# BalanceCar.net
KiCad netlist of a schematic drawn in Altium Designer
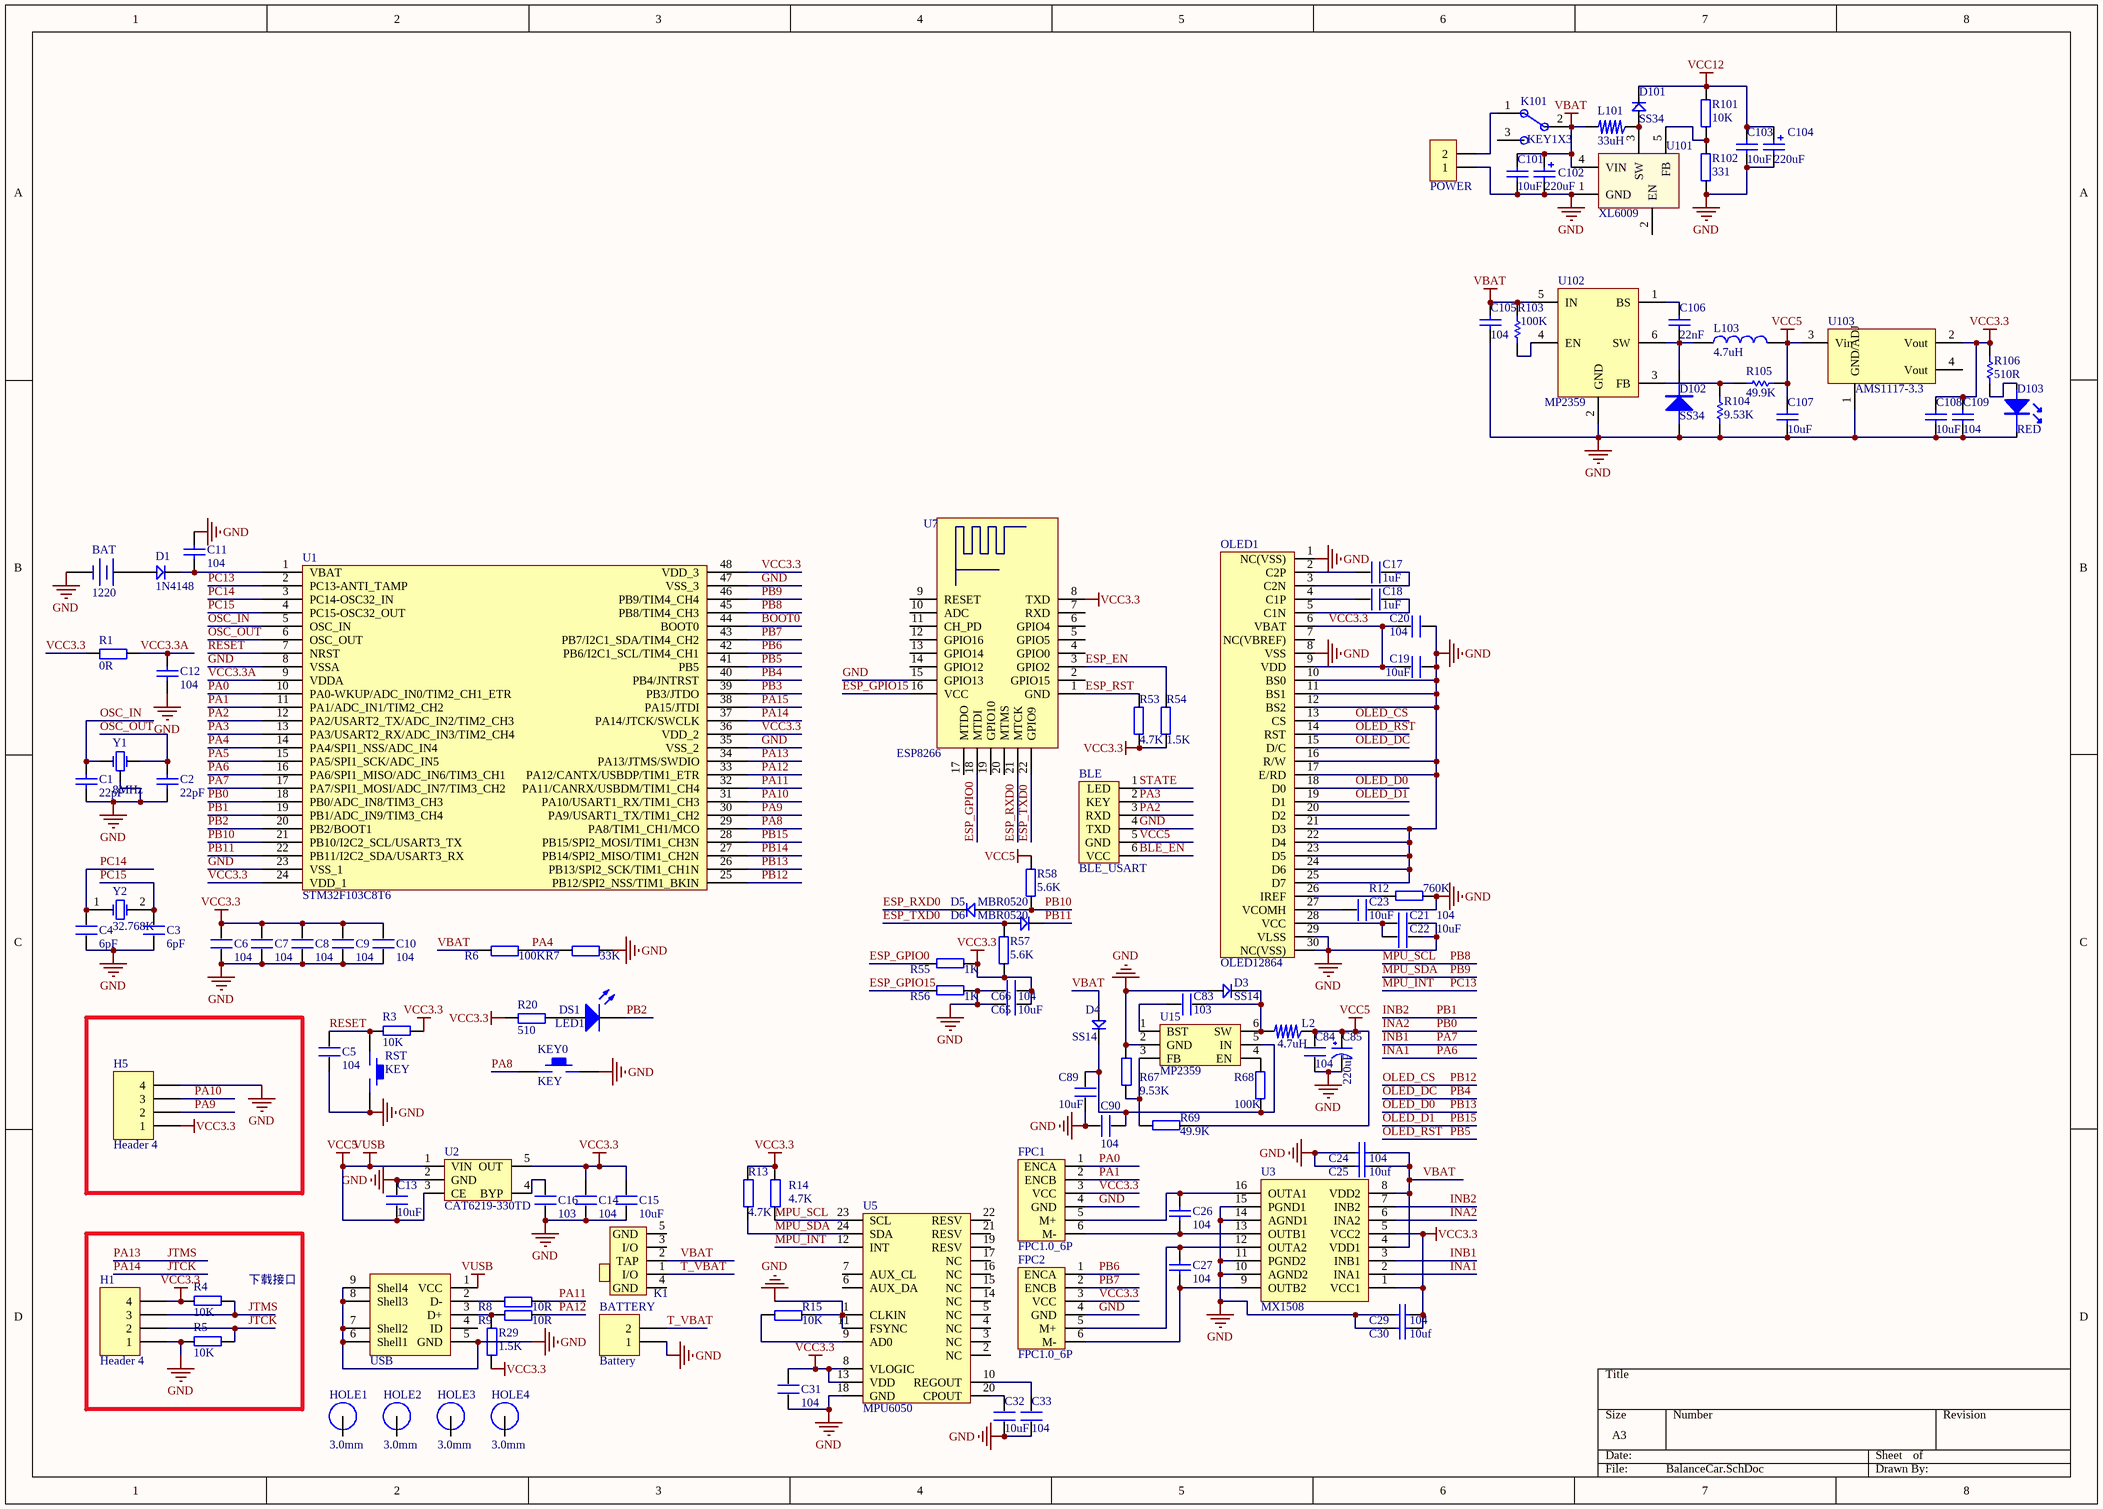
[diagram p0: BalanceCar.SchDoc]

(export (version "E")
  (design (tool "Eeschema 10.0.6"))
  (components
    (comp (ref "BAT")
      (value "1220")
      (footprint "CR1220_B")
      (description "微型电池")
      (libsource (lib "IMX6UL_ALPHA(底板)_V2.0") (part "CR-3V"))
    )
    (comp (ref "BATTERY")
      (value "Battery")
      (footprint "HDR2.54-LI-2P")
      (description "Header, 2-Pin")
      (fields (field (name "PUBLISHER") "Altium Limited"))
      (libsource (lib "WarShip V3 STM32103封装库") (part "Header 2"))
    )
    (comp (ref "BLE")
      (value "BLE_USART")
      (footprint "HEAD6")
      (description "ATK-HC05")
      (libsource (lib "阿波罗STM32F4&F7&H7底板封装库") (part "ATK-HC05"))
    )
    (comp (ref "C1") (value "22pF") (footprint "C 0603_M") (libsource (lib "L476") (part "CAP")))
    (comp (ref "C2") (value "22pF") (footprint "C 0603_M") (libsource (lib "L476") (part "CAP")))
    (comp (ref "C3")
      (value "6pF")
      (footprint "C 0603_M")
      (libsource (lib "WarShip V3 STM32103封装库") (part "C"))
    )
    (comp (ref "C4")
      (value "6pF")
      (footprint "C 0603_M")
      (libsource (lib "WarShip V3 STM32103封装库") (part "C"))
    )
    (comp (ref "C5")
      (value "104")
      (footprint "C 0603_M")
      (libsource (lib "WarShip V3 STM32103封装库") (part "C"))
    )
    (comp (ref "C6")
      (value "104")
      (footprint "C 0603_M")
      (libsource (lib "WarShip V3 STM32103封装库") (part "C"))
    )
    (comp (ref "C7")
      (value "104")
      (footprint "C 0603_M")
      (libsource (lib "WarShip V3 STM32103封装库") (part "C"))
    )
    (comp (ref "C8")
      (value "104")
      (footprint "C 0603_M")
      (libsource (lib "WarShip V3 STM32103封装库") (part "C"))
    )
    (comp (ref "C9")
      (value "104")
      (footprint "C 0603_M")
      (libsource (lib "WarShip V3 STM32103封装库") (part "C"))
    )
    (comp (ref "C10")
      (value "104")
      (footprint "C 0603_M")
      (libsource (lib "WarShip V3 STM32103封装库") (part "C"))
    )
    (comp (ref "C11") (value "104") (footprint "C 0603_M") (libsource (lib "L476") (part "CAP")))
    (comp (ref "C12") (value "104") (footprint "C 0603_M") (libsource (lib "L476") (part "CAP")))
    (comp (ref "C13")
      (value "10uF")
      (footprint "C 0603_M")
      (libsource (lib "WarShip V3 STM32103封装库") (part "C"))
    )
    (comp (ref "C14")
      (value "104")
      (footprint "C 0603_M")
      (libsource (lib "WarShip V3 STM32103封装库") (part "C"))
    )
    (comp (ref "C15")
      (value "10uF")
      (footprint "C 0603_M")
      (libsource (lib "WarShip V3 STM32103封装库") (part "C"))
    )
    (comp (ref "C16")
      (value "103")
      (footprint "C 0603_M")
      (libsource (lib "WarShip V3 STM32103封装库") (part "C"))
    )
    (comp (ref "C17")
      (value "1uF")
      (footprint "C 0603_M")
      (libsource (lib "WarShip V3 STM32103封装库") (part "C"))
    )
    (comp (ref "C18")
      (value "1uF")
      (footprint "C 0603_M")
      (libsource (lib "WarShip V3 STM32103封装库") (part "C"))
    )
    (comp (ref "C19")
      (value "10uF")
      (footprint "C 0603_M")
      (libsource (lib "WarShip V3 STM32103封装库") (part "C"))
    )
    (comp (ref "C20")
      (value "104")
      (footprint "C 0603_M")
      (libsource (lib "WarShip V3 STM32103封装库") (part "C"))
    )
    (comp (ref "C21")
      (value "10uF")
      (footprint "C 0603_M")
      (libsource (lib "WarShip V3 STM32103封装库") (part "C"))
    )
    (comp (ref "C22")
      (value "104")
      (footprint "C 0603_M")
      (libsource (lib "WarShip V3 STM32103封装库") (part "C"))
    )
    (comp (ref "C23")
      (value "10uF")
      (footprint "C 0603_M")
      (libsource (lib "WarShip V3 STM32103封装库") (part "C"))
    )
    (comp (ref "C24") (value "104") (footprint "C 0603_M") (libsource (lib "L476") (part "CAP")))
    (comp (ref "C25") (value "10uf") (footprint "C 0603_M") (libsource (lib "L476") (part "CAP")))
    (comp (ref "C26") (value "104") (footprint "C 0603_M") (libsource (lib "L476") (part "CAP")))
    (comp (ref "C27") (value "104") (footprint "C 0603_M") (libsource (lib "L476") (part "CAP")))
    (comp (ref "C29") (value "104") (footprint "C 0603_M") (libsource (lib "L476") (part "CAP")))
    (comp (ref "C30") (value "10uf") (footprint "C 0603_M") (libsource (lib "L476") (part "CAP")))
    (comp (ref "C31")
      (value "104")
      (footprint "C 0603_M")
      (libsource (lib "WarShip V3 STM32103封装库") (part "C"))
    )
    (comp (ref "C32")
      (value "10uF")
      (footprint "C 0603_M")
      (libsource (lib "WarShip V3 STM32103封装库") (part "C"))
    )
    (comp (ref "C33")
      (value "104")
      (footprint "C 0603_M")
      (libsource (lib "WarShip V3 STM32103封装库") (part "C"))
    )
    (comp (ref "C65") (value "10uF") (footprint "C 0603_M") (libsource (lib "ATK-OV5640摄像头模块封装库") (part "C")))
    (comp (ref "C66") (value "104") (footprint "C 0603_M") (libsource (lib "ATK-OV5640摄像头模块封装库") (part "C")))
    (comp (ref "C83") (value "103") (footprint "C 0603_M") (libsource (lib "ALIENTEK_COMPONENT") (part "C")))
    (comp (ref "C84") (value "104") (footprint "C 0603_M") (libsource (lib "MYCOMLIB") (part "C")))
    (comp (ref "C85") (value "220uF") (footprint "CM D(6.3*5.4)") (libsource (lib "MYCOMLIB") (part "CAP")))
    (comp (ref "C89") (value "10uF") (footprint "C 1206_L") (libsource (lib "ALIENTEK_COMPONENT") (part "C")))
    (comp (ref "C90") (value "104") (footprint "C 0603_M") (libsource (lib "MYCOMLIB") (part "C")))
    (comp (ref "C101")
      (value "10uF")
      (footprint "C 1210_M")
      (description "Capacitor")
      (fields (field (name "Comment") "Cap") (field (name "PUBLISHER") "Altium Limited"))
      (libsource (lib "YS_BDC_V1") (part "Cap_1"))
    )
    (comp (ref "C102")
      (value "220uF")
      (footprint "CAP 3.5*8*11.5 - BK")
      (description "Polarized Capacitor (Radial)")
      (fields (field (name "Comment") "Cap Pol") (field (name "PUBLISHER") "Altium Limited"))
      (libsource (lib "YS_BDC_V1") (part "Cap Pol_1"))
    )
    (comp (ref "C103")
      (value "10uF")
      (footprint "C 1210_M")
      (description "Capacitor")
      (fields (field (name "Comment") "Cap") (field (name "PUBLISHER") "Altium Limited"))
      (libsource (lib "YS_BDC_V1") (part "Cap_1"))
    )
    (comp (ref "C104")
      (value "220uF")
      (footprint "CAP 3.5*8*11.5 - BK")
      (description "Polarized Capacitor (Radial)")
      (fields (field (name "Comment") "Cap Pol") (field (name "PUBLISHER") "Altium Limited"))
      (libsource (lib "YS_BDC_V1") (part "Cap Pol_1"))
    )
    (comp (ref "C105")
      (value "104")
      (footprint "C 0603_M")
      (description "Capacitor")
      (fields (field (name "Comment") "Cap") (field (name "PUBLISHER") "Altium Limited"))
      (libsource (lib "YS_BLDC&PMSM") (part "Cap"))
    )
    (comp (ref "C106")
      (value "22nF")
      (footprint "C 0603_M")
      (description "Capacitor")
      (fields (field (name "Comment") "Cap") (field (name "PUBLISHER") "Altium Limited"))
      (libsource (lib "YS_BLDC&PMSM") (part "Cap"))
    )
    (comp (ref "C107")
      (value "10uF")
      (footprint "C 1210_M")
      (description "Capacitor")
      (fields (field (name "Comment") "Cap") (field (name "PUBLISHER") "Altium Limited"))
      (libsource (lib "YS_BDC_V1") (part "Cap_1"))
    )
    (comp (ref "C108")
      (value "10uF")
      (footprint "C 1210_M")
      (description "Capacitor")
      (fields (field (name "Comment") "Cap") (field (name "PUBLISHER") "Altium Limited"))
      (libsource (lib "YS_BDC_V1") (part "Cap_1"))
    )
    (comp (ref "C109")
      (value "104")
      (footprint "C 0603_M")
      (description "Capacitor")
      (fields (field (name "Comment") "Cap") (field (name "PUBLISHER") "Altium Limited"))
      (libsource (lib "YS_BLDC&PMSM") (part "Cap"))
    )
    (comp (ref "D1")
      (value "1N4148")
      (footprint "MINI_MELF (LL34)")
      (libsource (lib "阿波罗STM32F4&F7底板封装库") (part "D"))
    )
    (comp (ref "D3")
      (value "SS14")
      (footprint "SMA")
      (description "1N4148")
      (libsource (lib "MYCOMLIB") (part "D"))
    )
    (comp (ref "D4")
      (value "SS14")
      (footprint "SMA")
      (description "1N4148")
      (libsource (lib "MYCOMLIB") (part "D"))
    )
    (comp (ref "D5")
      (value "MBR0520")
      (footprint "SOD-123")
      (description "1N4148")
      (libsource (lib "ESP8266V1.2") (part "D"))
    )
    (comp (ref "D6")
      (value "MBR0520")
      (footprint "SOD-123")
      (description "1N4148")
      (libsource (lib "ESP8266V1.2") (part "D"))
    )
    (comp (ref "D101") (value "SS34") (footprint "SMA") (libsource (lib "阿波罗STM32F4&F7&H7底板封装库") (part "D")))
    (comp (ref "D102")
      (value "SS34")
      (footprint "SMA")
      (description "Diode")
      (libsource (lib "YS_BDC_V1") (part "DIODE_1"))
    )
    (comp (ref "D103") (value "RED") (footprint "LED 0805R") (libsource (lib "YS_BLDC&PMSM") (part "LED")))
    (comp (ref "DS1")
      (value "LED1")
      (footprint "LED 0603R")
      (description "Typical RED, GREEN, YELLOW, AMBER GaAs LED")
      (fields (field (name "PUBLISHER") "Altium Limited"))
      (libsource (lib "WarShip V3 STM32103封装库") (part "LED2"))
    )
    (comp (ref "FPC1")
      (value "FPC1.0_6P")
      (footprint "FPC_1.0_6P")
      (libsource (lib "MOTOR_FPC") (part "FPC"))
    )
    (comp (ref "FPC2")
      (value "FPC1.0_6P")
      (footprint "FPC_1.0_6P")
      (libsource (lib "MOTOR_FPC") (part "FPC"))
    )
    (comp (ref "H1")
      (value "Header 4")
      (footprint "HDR2.54-LI-4P")
      (description "Header, 4-Pin")
      (fields (field (name "PUBLISHER") "Altium Limited"))
      (libsource (lib "WarShip V3 STM32103封装库") (part "Header 4"))
    )
    (comp (ref "H5")
      (value "Header 4")
      (footprint "HDR2.54-LI-4P")
      (description "Header, 4-Pin")
      (fields (field (name "PUBLISHER") "Altium Limited"))
      (libsource (lib "WarShip V3 STM32103封装库") (part "Header 4"))
    )
    (comp (ref "HOLE1")
      (value "3.0mm")
      (footprint "HOLE-M3")
      (fields (field (name "Comment") "HOLE"))
      (libsource (lib "YS_BDC_V1") (part "HOLE"))
    )
    (comp (ref "HOLE2")
      (value "3.0mm")
      (footprint "HOLE-M3")
      (fields (field (name "Comment") "HOLE"))
      (libsource (lib "YS_BDC_V1") (part "HOLE"))
    )
    (comp (ref "HOLE3")
      (value "3.0mm")
      (footprint "HOLE-M3")
      (fields (field (name "Comment") "HOLE"))
      (libsource (lib "YS_BDC_V1") (part "HOLE"))
    )
    (comp (ref "HOLE4")
      (value "3.0mm")
      (footprint "HOLE-M3")
      (fields (field (name "Comment") "HOLE"))
      (libsource (lib "YS_BDC_V1") (part "HOLE"))
    )
    (comp (ref "K1")
      (value "BUTTON_DIP3")
      (footprint "BTN8.8*4.6")
      (description "拨动开关SS-12F44")
      (libsource (lib "Pandora_STM32L4_Board_V2.4") (part "BUTTON_DIP3"))
    )
    (comp (ref "K101")
      (value "KEY1X3")
      (footprint "PKEY")
      (libsource (lib "IMX6UL_ALPHA(底板)_V2.0") (part "PKEY"))
    )
    (comp (ref "KEY0")
      (value "KEY")
      (footprint "TSW SMD-3*6*2.5")
      (libsource (lib "STM32F429核心板封装库") (part "KEY_M"))
    )
    (comp (ref "L2")
      (value "4.7uH")
      (footprint "CDRH73")
      (libsource (lib "ALIENTEK_COMPONENT") (part "L_SOP"))
    )
    (comp (ref "L101")
      (value "33uH")
      (footprint "L_SOP74")
      (libsource (lib "阿波罗STM32F4&F7&H7底板封装库") (part "L_SOP"))
    )
    (comp (ref "L103")
      (value "4.7uH")
      (footprint "CD73")
      (fields (field (name "Comment") "Inductance"))
      (libsource (lib "YS_BDC_V1") (part "Inductance"))
    )
    (comp (ref "OLED1")
      (value "OLED12864")
      (footprint "OLED12864")
      (libsource (lib "OLED模块封装库") (part "OLED12864"))
    )
    (comp (ref "POWER")
      (value "SPKL")
      (footprint "XH2.54-2P_H")
      (description "2P接插件")
      (libsource (lib "IMX6UL_ALPHA(底板)_V2.0") (part "Header 2"))
    )
    (comp (ref "R1")
      (value "0R")
      (footprint "R 0603_M")
      (libsource (lib "WarShip V3 STM32103封装库") (part "R"))
    )
    (comp (ref "R3")
      (value "10K")
      (footprint "R 0603_M")
      (libsource (lib "WarShip V3 STM32103封装库") (part "R"))
    )
    (comp (ref "R4")
      (value "10K")
      (footprint "R 0603_M")
      (libsource (lib "WarShip V3 STM32103封装库") (part "R"))
    )
    (comp (ref "R5")
      (value "10K")
      (footprint "R 0603_M")
      (libsource (lib "WarShip V3 STM32103封装库") (part "R"))
    )
    (comp (ref "R6")
      (value "100K")
      (footprint "R 0603_M")
      (libsource (lib "WarShip V3 STM32103封装库") (part "R"))
    )
    (comp (ref "R7")
      (value "33K")
      (footprint "R 0603_M")
      (libsource (lib "WarShip V3 STM32103封装库") (part "R"))
    )
    (comp (ref "R8")
      (value "10R")
      (footprint "R 0603_M")
      (libsource (lib "WarShip V3 STM32103封装库") (part "R"))
    )
    (comp (ref "R9")
      (value "10R")
      (footprint "R 0603_M")
      (libsource (lib "WarShip V3 STM32103封装库") (part "R"))
    )
    (comp (ref "R12")
      (value "760K")
      (footprint "R 0603_M")
      (libsource (lib "WarShip V3 STM32103封装库") (part "R"))
    )
    (comp (ref "R13")
      (value "4.7K")
      (footprint "R 0603_M")
      (libsource (lib "WarShip V3 STM32103封装库") (part "R"))
    )
    (comp (ref "R14")
      (value "4.7K")
      (footprint "R 0603_M")
      (libsource (lib "WarShip V3 STM32103封装库") (part "R"))
    )
    (comp (ref "R15")
      (value "10K")
      (footprint "R 0603_M")
      (libsource (lib "WarShip V3 STM32103封装库") (part "R"))
    )
    (comp (ref "R20")
      (value "510")
      (footprint "R 0603_M")
      (libsource (lib "WarShip V3 STM32103封装库") (part "R"))
    )
    (comp (ref "R29")
      (value "1.5K")
      (footprint "R 0603_M")
      (libsource (lib "WarShip V3 STM32103封装库") (part "R"))
    )
    (comp (ref "R53")
      (value "4.7K")
      (footprint "R 0603_M")
      (libsource (lib "WarShip V3 STM32103封装库") (part "R"))
    )
    (comp (ref "R54")
      (value "1.5K")
      (footprint "R 0603_M")
      (libsource (lib "WarShip V3 STM32103封装库") (part "R"))
    )
    (comp (ref "R55")
      (value "1K")
      (footprint "R 0603_M")
      (libsource (lib "WarShip V3 STM32103封装库") (part "R"))
    )
    (comp (ref "R56")
      (value "1K")
      (footprint "R 0603_M")
      (libsource (lib "WarShip V3 STM32103封装库") (part "R"))
    )
    (comp (ref "R57")
      (value "5.6K")
      (footprint "R 0603_M")
      (libsource (lib "WarShip V3 STM32103封装库") (part "R"))
    )
    (comp (ref "R58")
      (value "5.6K")
      (footprint "R 0603_M")
      (libsource (lib "WarShip V3 STM32103封装库") (part "R"))
    )
    (comp (ref "R67")
      (value "9.53K")
      (footprint "R 0603_M")
      (libsource (lib "ALIENTEK_COMPONENT") (part "R"))
    )
    (comp (ref "R68") (value "100K") (footprint "R 0603_M") (libsource (lib "ALIENTEK_COMPONENT") (part "R")))
    (comp (ref "R69")
      (value "49.9K")
      (footprint "R 0603_M")
      (libsource (lib "ALIENTEK_COMPONENT") (part "R"))
    )
    (comp (ref "R101") (value "10K") (footprint "3296W") (libsource (lib "阿波罗STM32F4&F7&H7底板封装库") (part "R")))
    (comp (ref "R102")
      (value "331")
      (footprint "R 0603_M")
      (libsource (lib "阿波罗STM32F4&F7&H7底板封装库") (part "R"))
    )
    (comp (ref "R103")
      (value "100K")
      (footprint "R 0603_M")
      (description "Resistor")
      (fields (field (name "Comment") "Res1") (field (name "PUBLISHER") "Altium Limited"))
      (libsource (lib "YS_BLDC&PMSM") (part "Res1"))
    )
    (comp (ref "R104")
      (value "9.53K")
      (footprint "R 0603_M")
      (description "Resistor")
      (fields (field (name "Comment") "Res1") (field (name "PUBLISHER") "Altium Limited"))
      (libsource (lib "YS_BLDC&PMSM") (part "Res1"))
    )
    (comp (ref "R105")
      (value "49.9K")
      (footprint "R 0603_M")
      (description "Resistor")
      (fields (field (name "Comment") "Res1") (field (name "PUBLISHER") "Altium Limited"))
      (libsource (lib "YS_BLDC&PMSM") (part "Res1"))
    )
    (comp (ref "R106")
      (value "510R")
      (footprint "R 0603_M")
      (description "Resistor")
      (fields (field (name "Comment") "Res1") (field (name "PUBLISHER") "Altium Limited"))
      (libsource (lib "YS_BLDC&PMSM") (part "Res1"))
    )
    (comp (ref "RST") (value "KEY") (footprint "TSW SMD-3*6*2.5") (libsource (lib "") (part "KEY_M_1")))
    (comp (ref "U1")
      (value "STM32F103C8T6")
      (footprint "LQFP-48PIN")
      (libsource (lib "Pandora_STM32L4_Board_V2.4") (part "U-STM32F103C8T6"))
    )
    (comp (ref "U2")
      (value "CAT6219-330TD")
      (footprint "SOT23-5M")
      (description "3.3V 500mA LDO")
      (libsource (lib "STM32H743核心板封装库") (part "CAT6219-330TD"))
    )
    (comp (ref "U3") (value "MX1508") (footprint "SOP16N_M") (libsource (lib "fan") (part "Component_1")))
    (comp (ref "U5")
      (value "MPU6050")
      (footprint "QFN24 4x4_N")
      (description "9轴运动处理传感器")
      (libsource (lib "ATK-MPU6050六轴传感器模块") (part "MPU6050"))
    )
    (comp (ref "U7") (value "ESP8266") (footprint "ESP_12E") (libsource (lib "ESP8266V1.2") (part "ESP8266")))
    (comp (ref "U15")
      (value "MP2359")
      (footprint "SOT23-6M")
      (description "DC DC Step Down IC")
      (libsource (lib "ALIENTEK_COMPONENT") (part "MP2359"))
    )
    (comp (ref "U101") (value "XL6009") (footprint "TO-263-5") (libsource (lib "POWER") (part "XL6009")))
    (comp (ref "U102")
      (value "MP2359")
      (footprint "SOT23-6M")
      (description "MP2359DJ-LF-Z")
      (libsource (lib "YS_BDC_V1") (part "MP2359"))
    )
    (comp (ref "U103")
      (value "AMS1117-3.3")
      (footprint "SOT223_N")
      (description "LDO 3.3V")
      (libsource (lib "YS_BLDC&PMSM") (part "AMS1117-3.3"))
    )
    (comp (ref "USB")
      (value "J-MICRO-USB-5S")
      (footprint "USB-AB-5S")
      (description "Micro USB 5.9有柱脚长1.25加长针")
      (libsource (lib "Pandora_STM32L4_Board_V2.4") (part "J-MICRO-USB-5S"))
    )
    (comp (ref "Y1")
      (value "8MHz")
      (footprint "Y-XTAL-3215-3P")
      (description "XTAL,3215,8MHz")
      (libsource (lib "Pandora_STM32L4_Board_V2.4") (part "Y-3215-8M"))
    )
    (comp (ref "Y2")
      (value "32.768K")
      (footprint "OSC 3215-2P")
      (description "Crystal Oscillator")
      (fields (field (name "PUBLISHER") "Altium Limited"))
      (libsource (lib "WarShip V3 STM32103封装库") (part "XTAL"))
    )
  )
  (nets
    (net (code "1") (name "/BLE_EN") (class "Default")
      (node (ref "BLE") (pin "6") (pinfunction "VCC_6") (pintype "passive"))
    )
    (net (code "2") (name "/BOOT0") (class "Default")
      (node (ref "U1") (pin "44") (pinfunction "BOOT0_44") (pintype "passive"))
    )
    (net (code "3") (name "/ESP_EN") (class "Default")
      (node (ref "R54") (pin "1") (pintype "passive"))
      (node (ref "U7") (pin "3") (pinfunction "GPIO2_3") (pintype "passive"))
    )
    (net (code "4") (name "/ESP_GPIO0") (class "Default")
      (node (ref "R55") (pin "2") (pintype "passive"))
      (node (ref "U7") (pin "18") (pinfunction "MTDI_18") (pintype "passive"))
    )
    (net (code "5") (name "/ESP_GPIO15") (class "Default")
      (node (ref "R56") (pin "2") (pintype "passive"))
      (node (ref "U7") (pin "16") (pinfunction "VCC_16") (pintype "passive"))
    )
    (net (code "6") (name "/ESP_RST") (class "Default")
      (node (ref "R53") (pin "1") (pintype "passive"))
      (node (ref "U7") (pin "1") (pinfunction "GND_1") (pintype "open_emitter"))
    )
    (net (code "7") (name "/ESP_RXD0") (class "Default")
      (node (ref "D5") (pin "2") (pintype "passive"))
      (node (ref "U7") (pin "21") (pinfunction "MTCK_21") (pintype "passive"))
    )
    (net (code "8") (name "/ESP_TXD0") (class "Default")
      (node (ref "D6") (pin "1") (pintype "passive"))
      (node (ref "R57") (pin "1") (pintype "passive"))
      (node (ref "U7") (pin "22") (pinfunction "GPIO9_22") (pintype "passive"))
    )
    (net (code "9") (name "/INA1") (class "Default")
      (node (ref "U1") (pin "16") (pinfunction "PA6/SPI1_MISO/ADC_IN6/TIM3_CH1_16") (pintype "passive"))
      (node (ref "U3") (pin "2") (pinfunction "INA1_2") (pintype "passive"))
    )
    (net (code "10") (name "/INA2") (class "Default")
      (node (ref "U1") (pin "18") (pinfunction "PB0/ADC_IN8/TIM3_CH3_18") (pintype "passive"))
      (node (ref "U3") (pin "6") (pinfunction "INA2_6") (pintype "passive"))
    )
    (net (code "11") (name "/INB1") (class "Default")
      (node (ref "U1") (pin "17") (pinfunction "PA7/SPI1_MOSI/ADC_IN7/TIM3_CH2_17") (pintype "passive"))
      (node (ref "U3") (pin "3") (pinfunction "INB1_3") (pintype "passive"))
    )
    (net (code "12") (name "/INB2") (class "Default")
      (node (ref "U1") (pin "19") (pinfunction "PB1/ADC_IN9/TIM3_CH4_19") (pintype "passive"))
      (node (ref "U3") (pin "7") (pinfunction "INB2_7") (pintype "passive"))
    )
    (net (code "13") (name "/JTCK") (class "Default")
      (node (ref "H1") (pin "2") (pinfunction "2_2") (pintype "passive"))
      (node (ref "R5") (pin "1") (pintype "passive"))
      (node (ref "U1") (pin "37") (pinfunction "PA14/JTCK/SWCLK_37") (pintype "passive"))
    )
    (net (code "14") (name "/JTMS") (class "Default")
      (node (ref "H1") (pin "3") (pinfunction "3_3") (pintype "passive"))
      (node (ref "R4") (pin "1") (pintype "passive"))
      (node (ref "U1") (pin "34") (pinfunction "PA13/JTMS/SWDIO_34") (pintype "passive"))
    )
    (net (code "15") (name "/MPU_INT") (class "Default")
      (node (ref "U1") (pin "2") (pinfunction "PC13-ANTI_TAMP_2") (pintype "passive"))
      (node (ref "U5") (pin "12") (pinfunction "INT_12") (pintype "passive"))
    )
    (net (code "16") (name "/MPU_SCL") (class "Default")
      (node (ref "R14") (pin "1") (pintype "passive"))
      (node (ref "U1") (pin "45") (pinfunction "PB8/TIM4_CH3_45") (pintype "passive"))
      (node (ref "U5") (pin "23") (pinfunction "SCL_23") (pintype "passive"))
    )
    (net (code "17") (name "/MPU_SDA") (class "Default")
      (node (ref "R13") (pin "1") (pintype "passive"))
      (node (ref "U1") (pin "46") (pinfunction "PB9/TIM4_CH4_46") (pintype "passive"))
      (node (ref "U5") (pin "24") (pinfunction "SDA_24") (pintype "passive"))
    )
    (net (code "18") (name "/OLED_CS") (class "Default")
      (node (ref "OLED1") (pin "13") (pinfunction "CS_13") (pintype "passive"))
      (node (ref "U1") (pin "25") (pinfunction "PB12/SPI2_NSS/TIM1_BKIN_25") (pintype "passive"))
    )
    (net (code "19") (name "/OLED_D0") (class "Default")
      (node (ref "OLED1") (pin "18") (pinfunction "D0_18") (pintype "passive"))
      (node (ref "U1") (pin "26") (pinfunction "PB13/SPI2_SCK/TIM1_CH1N_26") (pintype "passive"))
    )
    (net (code "20") (name "/OLED_D1") (class "Default")
      (node (ref "OLED1") (pin "19") (pinfunction "D1_19") (pintype "passive"))
      (node (ref "U1") (pin "28") (pinfunction "PB15/SPI2_MOSI/TIM1_CH3N_28") (pintype "passive"))
    )
    (net (code "21") (name "/OLED_DC") (class "Default")
      (node (ref "OLED1") (pin "15") (pinfunction "D/C_15") (pintype "passive"))
      (node (ref "U1") (pin "40") (pinfunction "PB4/JNTRST_40") (pintype "passive"))
    )
    (net (code "22") (name "/OLED_RST") (class "Default")
      (node (ref "OLED1") (pin "14") (pinfunction "RST_14") (pintype "passive"))
      (node (ref "U1") (pin "41") (pinfunction "PB5_41") (pintype "passive"))
    )
    (net (code "23") (name "/OSC_IN") (class "Default")
      (node (ref "C1") (pin "2") (pinfunction "2_2") (pintype "passive"))
      (node (ref "U1") (pin "5") (pinfunction "OSC_IN_5") (pintype "passive"))
      (node (ref "Y1") (pin "1") (pinfunction "OSC1_1") (pintype "passive"))
    )
    (net (code "24") (name "/OSC_OUT") (class "Default")
      (node (ref "C2") (pin "2") (pinfunction "2_2") (pintype "passive"))
      (node (ref "U1") (pin "6") (pinfunction "OSC_OUT_6") (pintype "passive"))
      (node (ref "Y1") (pin "3") (pinfunction "OSC2_3") (pintype "passive"))
    )
    (net (code "25") (name "/PA0") (class "Default")
      (node (ref "FPC1") (pin "1") (pinfunction "ENCA_1") (pintype "passive"))
      (node (ref "U1") (pin "10") (pinfunction "PA0-WKUP/ADC_IN0/TIM2_CH1_ETR_10") (pintype "passive"))
    )
    (net (code "26") (name "/PA1") (class "Default")
      (node (ref "FPC1") (pin "2") (pinfunction "ENCB_2") (pintype "passive"))
      (node (ref "U1") (pin "11") (pinfunction "PA1/ADC_IN1/TIM2_CH2_11") (pintype "passive"))
    )
    (net (code "27") (name "/PA2") (class "Default")
      (node (ref "BLE") (pin "3") (pinfunction "RXD_3") (pintype "passive"))
      (node (ref "U1") (pin "12") (pinfunction "PA2/USART2_TX/ADC_IN2/TIM2_CH3_12") (pintype "passive"))
    )
    (net (code "28") (name "/PA3") (class "Default")
      (node (ref "BLE") (pin "2") (pinfunction "KEY_2") (pintype "passive"))
      (node (ref "U1") (pin "13") (pinfunction "PA3/USART2_RX/ADC_IN3/TIM2_CH4_13") (pintype "passive"))
    )
    (net (code "29") (name "/PA4") (class "Default")
      (node (ref "R6") (pin "2") (pintype "passive"))
      (node (ref "R7") (pin "1") (pintype "passive"))
      (node (ref "U1") (pin "14") (pinfunction "PA4/SPI1_NSS/ADC_IN4_14") (pintype "passive"))
    )
    (net (code "30") (name "/PA5") (class "Default")
      (node (ref "U1") (pin "15") (pinfunction "PA5/SPI1_SCK/ADC_IN5_15") (pintype "passive"))
    )
    (net (code "31") (name "/PA8") (class "Default")
      (node (ref "KEY0") (pin "1") (pinfunction "1_1") (pintype "passive"))
      (node (ref "U1") (pin "29") (pinfunction "PA8/TIM1_CH1/MCO_29") (pintype "passive"))
    )
    (net (code "32") (name "/PA9") (class "Default")
      (node (ref "H5") (pin "2") (pinfunction "2_2") (pintype "passive"))
      (node (ref "U1") (pin "30") (pinfunction "PA9/USART1_TX/TIM1_CH2_30") (pintype "passive"))
    )
    (net (code "33") (name "/PA10") (class "Default")
      (node (ref "H5") (pin "3") (pinfunction "3_3") (pintype "passive"))
      (node (ref "U1") (pin "31") (pinfunction "PA10/USART1_RX/TIM1_CH3_31") (pintype "passive"))
    )
    (net (code "34") (name "/PA11") (class "Default")
      (node (ref "R8") (pin "2") (pintype "passive"))
      (node (ref "U1") (pin "32") (pinfunction "PA11/CANRX/USBDM/TIM1_CH4_32") (pintype "passive"))
    )
    (net (code "35") (name "/PA12") (class "Default")
      (node (ref "R9") (pin "2") (pintype "passive"))
      (node (ref "U1") (pin "33") (pinfunction "PA12/CANTX/USBDP/TIM1_ETR_33") (pintype "passive"))
    )
    (net (code "36") (name "/PA15") (class "Default")
      (node (ref "U1") (pin "38") (pinfunction "PA15/JTDI_38") (pintype "passive"))
    )
    (net (code "37") (name "/PB2") (class "Default")
      (node (ref "DS1") (pin "2") (pinfunction "K_2") (pintype "passive"))
      (node (ref "U1") (pin "20") (pinfunction "PB2/BOOT1_20") (pintype "passive"))
    )
    (net (code "38") (name "/PB3") (class "Default")
      (node (ref "U1") (pin "39") (pinfunction "PB3/JTDO_39") (pintype "passive"))
    )
    (net (code "39") (name "/PB6") (class "Default")
      (node (ref "FPC2") (pin "1") (pinfunction "ENCA_1") (pintype "passive"))
      (node (ref "U1") (pin "42") (pinfunction "PB6/I2C1_SCL/TIM4_CH1_42") (pintype "passive"))
    )
    (net (code "40") (name "/PB7") (class "Default")
      (node (ref "FPC2") (pin "2") (pinfunction "ENCB_2") (pintype "passive"))
      (node (ref "U1") (pin "43") (pinfunction "PB7/I2C1_SDA/TIM4_CH2_43") (pintype "passive"))
    )
    (net (code "41") (name "/PB10") (class "Default")
      (node (ref "D5") (pin "1") (pintype "passive"))
      (node (ref "R58") (pin "2") (pintype "passive"))
      (node (ref "U1") (pin "21") (pinfunction "PB10/I2C2_SCL/USART3_TX_21") (pintype "passive"))
    )
    (net (code "42") (name "/PB11") (class "Default")
      (node (ref "D6") (pin "2") (pintype "passive"))
      (node (ref "U1") (pin "22") (pinfunction "PB11/I2C2_SDA/USART3_RX_22") (pintype "passive"))
    )
    (net (code "43") (name "/PB14") (class "Default")
      (node (ref "U1") (pin "27") (pinfunction "PB14/SPI2_MISO/TIM1_CH2N_27") (pintype "passive"))
    )
    (net (code "44") (name "/PC14") (class "Default")
      (node (ref "C4") (pin "2") (pintype "passive"))
      (node (ref "U1") (pin "3") (pinfunction "PC14-OSC32_IN_3") (pintype "passive"))
      (node (ref "Y2") (pin "1") (pinfunction "OSC1_1") (pintype "passive"))
    )
    (net (code "45") (name "/PC15") (class "Default")
      (node (ref "C3") (pin "2") (pintype "passive"))
      (node (ref "U1") (pin "4") (pinfunction "PC15-OSC32_OUT_4") (pintype "passive"))
      (node (ref "Y2") (pin "2") (pinfunction "OSC2_2") (pintype "passive"))
    )
    (net (code "46") (name "/RESET") (class "Default")
      (node (ref "C5") (pin "2") (pintype "passive"))
      (node (ref "R3") (pin "2") (pintype "passive"))
      (node (ref "RST") (pin "1") (pinfunction "1_1") (pintype "passive"))
      (node (ref "U1") (pin "7") (pinfunction "NRST_7") (pintype "passive"))
    )
    (net (code "47") (name "/STATE") (class "Default")
      (node (ref "BLE") (pin "1") (pinfunction "LED_1") (pintype "passive"))
    )
    (net (code "48") (name "/T_VBAT") (class "Default")
      (node (ref "BATTERY") (pin "2") (pinfunction "2_2") (pintype "passive"))
      (node (ref "K1") (pin "1") (pinfunction "I/O_1") (pintype "passive"))
    )
    (net (code "49") (name "/VCC3.3A") (class "Default")
      (node (ref "C12") (pin "2") (pinfunction "2_2") (pintype "passive"))
      (node (ref "R1") (pin "2") (pintype "passive"))
      (node (ref "U1") (pin "9") (pinfunction "VDDA_9") (pintype "passive"))
    )
    (net (code "50") (name "GND") (class "Default")
      (node (ref "BAT") (pin "2") (pinfunction "DC-_2") (pintype "passive"))
      (node (ref "BATTERY") (pin "1") (pinfunction "1_1") (pintype "passive"))
      (node (ref "BLE") (pin "4") (pinfunction "TXD_4") (pintype "passive"))
      (node (ref "C1") (pin "1") (pinfunction "1_1") (pintype "passive"))
      (node (ref "C10") (pin "1") (pintype "passive"))
      (node (ref "C101") (pin "2") (pinfunction "2_2") (pintype "passive"))
      (node (ref "C102") (pin "2") (pinfunction "2_2") (pintype "passive"))
      (node (ref "C103") (pin "2") (pinfunction "2_2") (pintype "passive"))
      (node (ref "C104") (pin "2") (pinfunction "2_2") (pintype "passive"))
      (node (ref "C105") (pin "2") (pinfunction "2_2") (pintype "passive"))
      (node (ref "C107") (pin "1") (pinfunction "1_1") (pintype "passive"))
      (node (ref "C108") (pin "1") (pinfunction "1_1") (pintype "passive"))
      (node (ref "C109") (pin "2") (pinfunction "2_2") (pintype "passive"))
      (node (ref "C11") (pin "2") (pinfunction "2_2") (pintype "passive"))
      (node (ref "C12") (pin "1") (pinfunction "1_1") (pintype "passive"))
      (node (ref "C13") (pin "2") (pintype "passive"))
      (node (ref "C14") (pin "1") (pintype "passive"))
      (node (ref "C15") (pin "1") (pintype "passive"))
      (node (ref "C16") (pin "1") (pintype "passive"))
      (node (ref "C19") (pin "1") (pintype "passive"))
      (node (ref "C2") (pin "1") (pinfunction "1_1") (pintype "passive"))
      (node (ref "C20") (pin "1") (pintype "passive"))
      (node (ref "C21") (pin "1") (pintype "passive"))
      (node (ref "C22") (pin "1") (pintype "passive"))
      (node (ref "C23") (pin "1") (pintype "passive"))
      (node (ref "C24") (pin "1") (pinfunction "1_1") (pintype "passive"))
      (node (ref "C25") (pin "1") (pinfunction "1_1") (pintype "passive"))
      (node (ref "C29") (pin "1") (pinfunction "1_1") (pintype "passive"))
      (node (ref "C3") (pin "1") (pintype "passive"))
      (node (ref "C30") (pin "1") (pinfunction "1_1") (pintype "passive"))
      (node (ref "C31") (pin "1") (pintype "passive"))
      (node (ref "C32") (pin "1") (pintype "passive"))
      (node (ref "C33") (pin "1") (pintype "passive"))
      (node (ref "C4") (pin "1") (pintype "passive"))
      (node (ref "C5") (pin "1") (pintype "passive"))
      (node (ref "C6") (pin "1") (pintype "passive"))
      (node (ref "C65") (pin "1") (pintype "passive"))
      (node (ref "C66") (pin "1") (pintype "passive"))
      (node (ref "C7") (pin "1") (pintype "passive"))
      (node (ref "C8") (pin "1") (pintype "passive"))
      (node (ref "C84") (pin "1") (pintype "passive"))
      (node (ref "C85") (pin "2") (pinfunction "GND_2") (pintype "passive"))
      (node (ref "C89") (pin "1") (pintype "passive"))
      (node (ref "C9") (pin "1") (pintype "passive"))
      (node (ref "C90") (pin "1") (pintype "passive"))
      (node (ref "D102") (pin "1") (pinfunction "A_1") (pintype "passive"))
      (node (ref "D103") (pin "2") (pinfunction "2_2") (pintype "passive"))
      (node (ref "D3") (pin "1") (pintype "passive"))
      (node (ref "FPC1") (pin "4") (pinfunction "GND_4") (pintype "passive"))
      (node (ref "FPC2") (pin "4") (pinfunction "GND_4") (pintype "passive"))
      (node (ref "H1") (pin "1") (pinfunction "1_1") (pintype "passive"))
      (node (ref "H5") (pin "4") (pinfunction "4_4") (pintype "passive"))
      (node (ref "KEY0") (pin "2") (pinfunction "2_2") (pintype "passive"))
      (node (ref "OLED1") (pin "1") (pinfunction "NC(VSS)_1") (pintype "passive"))
      (node (ref "OLED1") (pin "10") (pinfunction "BS0_10") (pintype "passive"))
      (node (ref "OLED1") (pin "11") (pinfunction "BS1_11") (pintype "passive"))
      (node (ref "OLED1") (pin "12") (pinfunction "BS2_12") (pintype "passive"))
      (node (ref "OLED1") (pin "16") (pinfunction "R/W_16") (pintype "passive"))
      (node (ref "OLED1") (pin "17") (pinfunction "E/RD_17") (pintype "passive"))
      (node (ref "OLED1") (pin "21") (pinfunction "D3_21") (pintype "passive"))
      (node (ref "OLED1") (pin "22") (pinfunction "D4_22") (pintype "passive"))
      (node (ref "OLED1") (pin "23") (pinfunction "D5_23") (pintype "passive"))
      (node (ref "OLED1") (pin "24") (pinfunction "D6_24") (pintype "passive"))
      (node (ref "OLED1") (pin "25") (pinfunction "D7_25") (pintype "passive"))
      (node (ref "OLED1") (pin "29") (pinfunction "VLSS_29") (pintype "passive"))
      (node (ref "OLED1") (pin "30") (pinfunction "NC(VSS)_30") (pintype "passive"))
      (node (ref "OLED1") (pin "8") (pinfunction "VSS_8") (pintype "passive"))
      (node (ref "POWER") (pin "1") (pinfunction "1_1") (pintype "passive"))
      (node (ref "R102") (pin "2") (pintype "passive"))
      (node (ref "R104") (pin "2") (pinfunction "2_2") (pintype "passive"))
      (node (ref "R12") (pin "1") (pintype "passive"))
      (node (ref "R15") (pin "2") (pintype "passive"))
      (node (ref "R5") (pin "2") (pintype "passive"))
      (node (ref "R56") (pin "1") (pintype "passive"))
      (node (ref "R67") (pin "2") (pintype "passive"))
      (node (ref "R7") (pin "2") (pintype "passive"))
      (node (ref "RST") (pin "2") (pinfunction "2_2") (pintype "passive"))
      (node (ref "U1") (pin "23") (pinfunction "VSS_1_23") (pintype "passive"))
      (node (ref "U1") (pin "35") (pinfunction "VSS_2_35") (pintype "passive"))
      (node (ref "U1") (pin "47") (pinfunction "VSS_3_47") (pintype "passive"))
      (node (ref "U1") (pin "8") (pinfunction "VSSA_8") (pintype "passive"))
      (node (ref "U101") (pin "1") (pinfunction "GND_1") (pintype "passive"))
      (node (ref "U102") (pin "2") (pinfunction "GND_2") (pintype "passive"))
      (node (ref "U103") (pin "1") (pinfunction "GND/ADJ_1") (pintype "passive"))
      (node (ref "U15") (pin "2") (pinfunction "GND_2") (pintype "passive"))
      (node (ref "U2") (pin "2") (pinfunction "GND_2") (pintype "passive"))
      (node (ref "U3") (pin "10") (pinfunction "AGND2_10") (pintype "passive"))
      (node (ref "U3") (pin "11") (pinfunction "PGND2_11") (pintype "passive"))
      (node (ref "U3") (pin "14") (pinfunction "AGND1_14") (pintype "passive"))
      (node (ref "U3") (pin "15") (pinfunction "PGND1_15") (pintype "passive"))
      (node (ref "U5") (pin "1") (pinfunction "CLKIN_1") (pintype "passive"))
      (node (ref "U5") (pin "11") (pinfunction "FSYNC_11") (pintype "passive"))
      (node (ref "U5") (pin "18") (pinfunction "GND_18") (pintype "passive"))
      (node (ref "U7") (pin "15") (pinfunction "GPIO13_15") (pintype "passive"))
      (node (ref "USB") (pin "5") (pinfunction "GND_5") (pintype "passive"))
      (node (ref "USB") (pin "6") (pinfunction "Shell1_6") (pintype "passive"))
      (node (ref "USB") (pin "7") (pinfunction "Shell2_7") (pintype "passive"))
      (node (ref "USB") (pin "8") (pinfunction "Shell3_8") (pintype "passive"))
      (node (ref "USB") (pin "9") (pinfunction "Shell4_9") (pintype "passive"))
      (node (ref "Y1") (pin "2") (pinfunction "GND_2") (pintype "passive"))
    )
    (net (code "51") (name "Net-(BAT-DC+)") (class "Default")
      (node (ref "BAT") (pin "1") (pinfunction "DC+_1") (pintype "passive"))
      (node (ref "D1") (pin "1") (pintype "passive"))
    )
    (net (code "52") (name "Net-(D102-K)") (class "Default")
      (node (ref "C106") (pin "2") (pinfunction "2_2") (pintype "passive"))
      (node (ref "D102") (pin "2") (pinfunction "K_2") (pintype "passive"))
      (node (ref "L103") (pin "1") (pintype "passive"))
      (node (ref "U102") (pin "6") (pinfunction "SW_6") (pintype "passive"))
    )
    (net (code "53") (name "Net-(D103-Pad1)") (class "Default")
      (node (ref "D103") (pin "1") (pinfunction "1_1") (pintype "passive"))
      (node (ref "R106") (pin "2") (pinfunction "2_2") (pintype "passive"))
    )
    (net (code "54") (name "Net-(DS1-A)") (class "Default")
      (node (ref "DS1") (pin "1") (pinfunction "A_1") (pintype "passive"))
      (node (ref "R20") (pin "2") (pintype "passive"))
    )
    (net (code "55") (name "Net-(FPC1-M+)") (class "Default")
      (node (ref "C26") (pin "2") (pinfunction "2_2") (pintype "passive"))
      (node (ref "FPC1") (pin "5") (pinfunction "M+_5") (pintype "passive"))
      (node (ref "U3") (pin "16") (pinfunction "OUTA1_16") (pintype "passive"))
    )
    (net (code "56") (name "Net-(FPC1-M-)") (class "Default")
      (node (ref "C26") (pin "1") (pinfunction "1_1") (pintype "passive"))
      (node (ref "FPC1") (pin "6") (pinfunction "M-_6") (pintype "passive"))
      (node (ref "U3") (pin "13") (pinfunction "OUTB1_13") (pintype "passive"))
    )
    (net (code "57") (name "Net-(FPC2-M+)") (class "Default")
      (node (ref "C27") (pin "2") (pinfunction "2_2") (pintype "passive"))
      (node (ref "FPC2") (pin "5") (pinfunction "M+_5") (pintype "passive"))
      (node (ref "U3") (pin "12") (pinfunction "OUTA2_12") (pintype "passive"))
    )
    (net (code "58") (name "Net-(FPC2-M-)") (class "Default")
      (node (ref "C27") (pin "1") (pinfunction "1_1") (pintype "passive"))
      (node (ref "FPC2") (pin "6") (pinfunction "M-_6") (pintype "passive"))
      (node (ref "U3") (pin "9") (pinfunction "OUTB2_9") (pintype "passive"))
    )
    (net (code "59") (name "Net-(K101-Pad1)") (class "Default")
      (node (ref "K101") (pin "1") (pintype "passive"))
      (node (ref "POWER") (pin "2") (pinfunction "2_2") (pintype "passive"))
    )
    (net (code "60") (name "Net-(OLED1-C1N)") (class "Default")
      (node (ref "C18") (pin "1") (pintype "passive"))
      (node (ref "OLED1") (pin "5") (pinfunction "C1N_5") (pintype "passive"))
    )
    (net (code "61") (name "Net-(OLED1-C1P)") (class "Default")
      (node (ref "C18") (pin "2") (pintype "passive"))
      (node (ref "OLED1") (pin "4") (pinfunction "C1P_4") (pintype "passive"))
    )
    (net (code "62") (name "Net-(OLED1-C2N)") (class "Default")
      (node (ref "C17") (pin "1") (pintype "passive"))
      (node (ref "OLED1") (pin "3") (pinfunction "C2N_3") (pintype "passive"))
    )
    (net (code "63") (name "Net-(OLED1-C2P)") (class "Default")
      (node (ref "C17") (pin "2") (pintype "passive"))
      (node (ref "OLED1") (pin "2") (pinfunction "C2P_2") (pintype "passive"))
    )
    (net (code "64") (name "Net-(OLED1-IREF)") (class "Default")
      (node (ref "OLED1") (pin "26") (pinfunction "IREF_26") (pintype "passive"))
      (node (ref "R12") (pin "2") (pintype "passive"))
    )
    (net (code "65") (name "Net-(OLED1-VCC)") (class "Default")
      (node (ref "C21") (pin "2") (pintype "passive"))
      (node (ref "C22") (pin "2") (pintype "passive"))
      (node (ref "OLED1") (pin "28") (pinfunction "VCC_28") (pintype "passive"))
    )
    (net (code "66") (name "Net-(OLED1-VCOMH)") (class "Default")
      (node (ref "C23") (pin "2") (pintype "passive"))
      (node (ref "OLED1") (pin "27") (pinfunction "VCOMH_27") (pintype "passive"))
    )
    (net (code "67") (name "Net-(U1-VBAT)") (class "Default")
      (node (ref "C11") (pin "1") (pinfunction "1_1") (pintype "passive"))
      (node (ref "D1") (pin "2") (pintype "passive"))
      (node (ref "U1") (pin "1") (pinfunction "VBAT_1") (pintype "passive"))
    )
    (net (code "68") (name "Net-(U2-BYP)") (class "Default")
      (node (ref "C16") (pin "2") (pintype "passive"))
      (node (ref "U2") (pin "4") (pinfunction "BYP_4") (pintype "passive"))
    )
    (net (code "69") (name "Net-(U5-AD0)") (class "Default")
      (node (ref "R15") (pin "1") (pintype "passive"))
      (node (ref "U5") (pin "9") (pinfunction "AD0_9") (pintype "passive"))
    )
    (net (code "70") (name "Net-(U5-CPOUT)") (class "Default")
      (node (ref "C32") (pin "2") (pintype "passive"))
      (node (ref "U5") (pin "20") (pinfunction "CPOUT_20") (pintype "passive"))
    )
    (net (code "71") (name "Net-(U5-REGOUT)") (class "Default")
      (node (ref "C33") (pin "2") (pintype "passive"))
      (node (ref "U5") (pin "10") (pinfunction "REGOUT_10") (pintype "passive"))
    )
    (net (code "72") (name "Net-(U15-BST)") (class "Default")
      (node (ref "C83") (pin "1") (pintype "passive"))
      (node (ref "U15") (pin "1") (pinfunction "BST_1") (pintype "passive"))
    )
    (net (code "73") (name "Net-(U15-EN)") (class "Default")
      (node (ref "R68") (pin "1") (pintype "passive"))
      (node (ref "U15") (pin "4") (pinfunction "EN_4") (pintype "passive"))
    )
    (net (code "74") (name "Net-(U15-FB)") (class "Default")
      (node (ref "R67") (pin "1") (pintype "passive"))
      (node (ref "R69") (pin "2") (pintype "passive"))
      (node (ref "U15") (pin "3") (pinfunction "FB_3") (pintype "passive"))
    )
    (net (code "75") (name "Net-(U15-IN)") (class "Default")
      (node (ref "C89") (pin "2") (pintype "passive"))
      (node (ref "C90") (pin "2") (pintype "passive"))
      (node (ref "D4") (pin "2") (pintype "passive"))
      (node (ref "R68") (pin "2") (pintype "passive"))
      (node (ref "U15") (pin "5") (pinfunction "IN_5") (pintype "passive"))
    )
    (net (code "76") (name "Net-(U15-SW)") (class "Default")
      (node (ref "C83") (pin "2") (pintype "passive"))
      (node (ref "D3") (pin "2") (pintype "passive"))
      (node (ref "L2") (pin "2") (pinfunction "2_2") (pintype "passive"))
      (node (ref "U15") (pin "6") (pinfunction "SW_6") (pintype "passive"))
    )
    (net (code "77") (name "Net-(U101-FB)") (class "Default")
      (node (ref "R101") (pin "2") (pintype "passive"))
      (node (ref "R102") (pin "1") (pintype "passive"))
      (node (ref "U101") (pin "5") (pinfunction "FB_5") (pintype "passive"))
    )
    (net (code "78") (name "Net-(U101-SW)") (class "Default")
      (node (ref "D101") (pin "1") (pintype "passive"))
      (node (ref "L101") (pin "1") (pinfunction "1_1") (pintype "passive"))
      (node (ref "U101") (pin "3") (pinfunction "SW_3") (pintype "passive"))
    )
    (net (code "79") (name "Net-(U102-BS)") (class "Default")
      (node (ref "C106") (pin "1") (pinfunction "1_1") (pintype "passive"))
      (node (ref "U102") (pin "1") (pinfunction "BS_1") (pintype "passive"))
    )
    (net (code "80") (name "Net-(U102-EN)") (class "Default")
      (node (ref "R103") (pin "1") (pinfunction "1_1") (pintype "passive"))
      (node (ref "U102") (pin "4") (pinfunction "EN_4") (pintype "passive"))
    )
    (net (code "81") (name "Net-(U102-FB)") (class "Default")
      (node (ref "R104") (pin "1") (pinfunction "1_1") (pintype "passive"))
      (node (ref "R105") (pin "2") (pinfunction "2_2") (pintype "passive"))
      (node (ref "U102") (pin "3") (pinfunction "FB_3") (pintype "passive"))
    )
    (net (code "82") (name "Net-(USB-D+)") (class "Default")
      (node (ref "R29") (pin "2") (pintype "passive"))
      (node (ref "R9") (pin "1") (pintype "passive"))
      (node (ref "USB") (pin "3") (pinfunction "D+_3") (pintype "passive"))
    )
    (net (code "83") (name "Net-(USB-D-)") (class "Default")
      (node (ref "R8") (pin "1") (pintype "passive"))
      (node (ref "USB") (pin "2") (pinfunction "D-_2") (pintype "passive"))
    )
    (net (code "84") (name "VBAT") (class "Default")
      (node (ref "C101") (pin "1") (pinfunction "1_1") (pintype "passive"))
      (node (ref "C102") (pin "1") (pinfunction "1_1") (pintype "passive"))
      (node (ref "C105") (pin "1") (pinfunction "1_1") (pintype "passive"))
      (node (ref "C24") (pin "2") (pinfunction "2_2") (pintype "passive"))
      (node (ref "C25") (pin "2") (pinfunction "2_2") (pintype "passive"))
      (node (ref "D4") (pin "1") (pintype "passive"))
      (node (ref "K1") (pin "2") (pinfunction "TAP_2") (pintype "passive"))
      (node (ref "K101") (pin "2") (pintype "passive"))
      (node (ref "L101") (pin "2") (pinfunction "2_2") (pintype "passive"))
      (node (ref "R103") (pin "2") (pinfunction "2_2") (pintype "passive"))
      (node (ref "R6") (pin "1") (pintype "passive"))
      (node (ref "U101") (pin "4") (pinfunction "VIN_4") (pintype "passive"))
      (node (ref "U102") (pin "5") (pinfunction "IN_5") (pintype "passive"))
      (node (ref "U3") (pin "4") (pinfunction "VDD1_4") (pintype "passive"))
      (node (ref "U3") (pin "8") (pinfunction "VDD2_8") (pintype "passive"))
    )
    (net (code "85") (name "VCC3.3") (class "Default")
      (node (ref "C10") (pin "2") (pintype "passive"))
      (node (ref "C108") (pin "2") (pinfunction "2_2") (pintype "passive"))
      (node (ref "C109") (pin "1") (pinfunction "1_1") (pintype "passive"))
      (node (ref "C14") (pin "2") (pintype "passive"))
      (node (ref "C15") (pin "2") (pintype "passive"))
      (node (ref "C19") (pin "2") (pintype "passive"))
      (node (ref "C20") (pin "2") (pintype "passive"))
      (node (ref "C29") (pin "2") (pinfunction "2_2") (pintype "passive"))
      (node (ref "C30") (pin "2") (pinfunction "2_2") (pintype "passive"))
      (node (ref "C31") (pin "2") (pintype "passive"))
      (node (ref "C6") (pin "2") (pintype "passive"))
      (node (ref "C65") (pin "2") (pintype "passive"))
      (node (ref "C66") (pin "2") (pintype "passive"))
      (node (ref "C7") (pin "2") (pintype "passive"))
      (node (ref "C8") (pin "2") (pintype "passive"))
      (node (ref "C9") (pin "2") (pintype "passive"))
      (node (ref "FPC1") (pin "3") (pinfunction "VCC_3") (pintype "passive"))
      (node (ref "FPC2") (pin "3") (pinfunction "VCC_3") (pintype "passive"))
      (node (ref "H1") (pin "4") (pinfunction "4_4") (pintype "passive"))
      (node (ref "H5") (pin "1") (pinfunction "1_1") (pintype "passive"))
      (node (ref "OLED1") (pin "6") (pinfunction "VBAT_6") (pintype "passive"))
      (node (ref "OLED1") (pin "9") (pinfunction "VDD_9") (pintype "passive"))
      (node (ref "R1") (pin "1") (pintype "passive"))
      (node (ref "R106") (pin "1") (pinfunction "1_1") (pintype "passive"))
      (node (ref "R13") (pin "2") (pintype "passive"))
      (node (ref "R14") (pin "2") (pintype "passive"))
      (node (ref "R20") (pin "1") (pintype "passive"))
      (node (ref "R29") (pin "1") (pintype "passive"))
      (node (ref "R3") (pin "1") (pintype "passive"))
      (node (ref "R4") (pin "2") (pintype "passive"))
      (node (ref "R53") (pin "2") (pintype "passive"))
      (node (ref "R54") (pin "2") (pintype "passive"))
      (node (ref "R55") (pin "1") (pintype "passive"))
      (node (ref "R57") (pin "2") (pintype "passive"))
      (node (ref "U1") (pin "24") (pinfunction "VDD_1_24") (pintype "passive"))
      (node (ref "U1") (pin "36") (pinfunction "VDD_2_36") (pintype "passive"))
      (node (ref "U1") (pin "48") (pinfunction "VDD_3_48") (pintype "passive"))
      (node (ref "U103") (pin "2") (pinfunction "Vout_2") (pintype "passive"))
      (node (ref "U2") (pin "5") (pinfunction "OUT_5") (pintype "passive"))
      (node (ref "U3") (pin "1") (pinfunction "VCC1_1") (pintype "passive"))
      (node (ref "U3") (pin "5") (pinfunction "VCC2_5") (pintype "passive"))
      (node (ref "U5") (pin "13") (pinfunction "VDD_13") (pintype "passive"))
      (node (ref "U5") (pin "8") (pinfunction "VLOGIC_8") (pintype "passive"))
      (node (ref "U7") (pin "8") (pinfunction "TXD_8") (pintype "passive"))
    )
    (net (code "86") (name "VCC5") (class "Default")
      (node (ref "BLE") (pin "5") (pinfunction "GND_5") (pintype "passive"))
      (node (ref "C107") (pin "2") (pinfunction "2_2") (pintype "passive"))
      (node (ref "C13") (pin "1") (pintype "passive"))
      (node (ref "C84") (pin "2") (pintype "passive"))
      (node (ref "C85") (pin "1") (pinfunction "VCC_1") (pintype "passive"))
      (node (ref "L103") (pin "2") (pintype "passive"))
      (node (ref "L2") (pin "1") (pinfunction "1_1") (pintype "passive"))
      (node (ref "R105") (pin "1") (pinfunction "1_1") (pintype "passive"))
      (node (ref "R58") (pin "1") (pintype "passive"))
      (node (ref "R69") (pin "1") (pintype "passive"))
      (node (ref "U103") (pin "3") (pinfunction "Vin_3") (pintype "passive"))
      (node (ref "U2") (pin "1") (pinfunction "VIN_1") (pintype "passive"))
      (node (ref "U2") (pin "3") (pinfunction "CE_3") (pintype "passive"))
      (node (ref "USB") (pin "1") (pinfunction "VCC_1") (pintype "passive"))
    )
    (net (code "87") (name "VCC12") (class "Default")
      (node (ref "C103") (pin "1") (pinfunction "1_1") (pintype "passive"))
      (node (ref "C104") (pin "1") (pinfunction "1_1") (pintype "passive"))
      (node (ref "D101") (pin "2") (pintype "passive"))
      (node (ref "R101") (pin "1") (pintype "passive"))
    )
    (net (code "88") (name "unconnected-(HOLE1-Pad1)") (class "Default")
      (node (ref "HOLE1") (pin "1") (pintype "passive"))
    )
    (net (code "89") (name "unconnected-(HOLE2-Pad1)") (class "Default")
      (node (ref "HOLE2") (pin "1") (pintype "passive"))
    )
    (net (code "90") (name "unconnected-(HOLE3-Pad1)") (class "Default")
      (node (ref "HOLE3") (pin "1") (pintype "passive"))
    )
    (net (code "91") (name "unconnected-(HOLE4-Pad1)") (class "Default")
      (node (ref "HOLE4") (pin "1") (pintype "passive"))
    )
    (net (code "92") (name "unconnected-(K1-GND-Pad4)") (class "Default")
      (node (ref "K1") (pin "4") (pinfunction "GND_4") (pintype "passive"))
    )
    (net (code "93") (name "unconnected-(K1-GND-Pad5)") (class "Default")
      (node (ref "K1") (pin "5") (pinfunction "GND_5") (pintype "passive"))
    )
    (net (code "94") (name "unconnected-(K1-I{slash}O-Pad3)") (class "Default")
      (node (ref "K1") (pin "3") (pinfunction "I/O_3") (pintype "passive"))
    )
    (net (code "95") (name "unconnected-(K101-Pad3)") (class "Default")
      (node (ref "K101") (pin "3") (pintype "passive"))
    )
    (net (code "96") (name "unconnected-(OLED1-D2-Pad20)") (class "Default")
      (node (ref "OLED1") (pin "20") (pinfunction "D2_20") (pintype "passive"))
    )
    (net (code "97") (name "unconnected-(OLED1-NC(VBREF)-Pad7)") (class "Default")
      (node (ref "OLED1") (pin "7") (pinfunction "NC(VBREF)_7") (pintype "passive"))
    )
    (net (code "98") (name "unconnected-(U5-AUX_CL-Pad7)") (class "Default")
      (node (ref "U5") (pin "7") (pinfunction "AUX_CL_7") (pintype "passive"))
    )
    (net (code "99") (name "unconnected-(U5-AUX_DA-Pad6)") (class "Default")
      (node (ref "U5") (pin "6") (pinfunction "AUX_DA_6") (pintype "passive"))
    )
    (net (code "100") (name "unconnected-(U5-NC-Pad2)") (class "Default")
      (node (ref "U5") (pin "2") (pinfunction "NC_2") (pintype "passive"))
    )
    (net (code "101") (name "unconnected-(U5-NC-Pad3)") (class "Default")
      (node (ref "U5") (pin "3") (pinfunction "NC_3") (pintype "passive"))
    )
    (net (code "102") (name "unconnected-(U5-NC-Pad4)") (class "Default")
      (node (ref "U5") (pin "4") (pinfunction "NC_4") (pintype "passive"))
    )
    (net (code "103") (name "unconnected-(U5-NC-Pad5)") (class "Default")
      (node (ref "U5") (pin "5") (pinfunction "NC_5") (pintype "passive"))
    )
    (net (code "104") (name "unconnected-(U5-NC-Pad14)") (class "Default")
      (node (ref "U5") (pin "14") (pinfunction "NC_14") (pintype "passive"))
    )
    (net (code "105") (name "unconnected-(U5-NC-Pad15)") (class "Default")
      (node (ref "U5") (pin "15") (pinfunction "NC_15") (pintype "passive"))
    )
    (net (code "106") (name "unconnected-(U5-NC-Pad16)") (class "Default")
      (node (ref "U5") (pin "16") (pinfunction "NC_16") (pintype "passive"))
    )
    (net (code "107") (name "unconnected-(U5-NC-Pad17)") (class "Default")
      (node (ref "U5") (pin "17") (pinfunction "NC_17") (pintype "passive"))
    )
    (net (code "108") (name "unconnected-(U5-RESV-Pad19)") (class "Default")
      (node (ref "U5") (pin "19") (pinfunction "RESV_19") (pintype "passive"))
    )
    (net (code "109") (name "unconnected-(U5-RESV-Pad21)") (class "Default")
      (node (ref "U5") (pin "21") (pinfunction "RESV_21") (pintype "passive"))
    )
    (net (code "110") (name "unconnected-(U5-RESV-Pad22)") (class "Default")
      (node (ref "U5") (pin "22") (pinfunction "RESV_22") (pintype "passive"))
    )
    (net (code "111") (name "unconnected-(U7-ADC-Pad10)") (class "Default")
      (node (ref "U7") (pin "10") (pinfunction "ADC_10") (pintype "passive"))
    )
    (net (code "112") (name "unconnected-(U7-CH_PD-Pad11)") (class "Default")
      (node (ref "U7") (pin "11") (pinfunction "CH_PD_11") (pintype "passive"))
    )
    (net (code "113") (name "unconnected-(U7-GPIO0-Pad4)") (class "Default")
      (node (ref "U7") (pin "4") (pinfunction "GPIO0_4") (pintype "passive"))
    )
    (net (code "114") (name "unconnected-(U7-GPIO4-Pad6)") (class "Default")
      (node (ref "U7") (pin "6") (pinfunction "GPIO4_6") (pintype "passive"))
    )
    (net (code "115") (name "unconnected-(U7-GPIO5-Pad5)") (class "Default")
      (node (ref "U7") (pin "5") (pinfunction "GPIO5_5") (pintype "passive"))
    )
    (net (code "116") (name "unconnected-(U7-GPIO10-Pad19)") (class "Default")
      (node (ref "U7") (pin "19") (pinfunction "GPIO10_19") (pintype "passive"))
    )
    (net (code "117") (name "unconnected-(U7-GPIO12-Pad14)") (class "Default")
      (node (ref "U7") (pin "14") (pinfunction "GPIO12_14") (pintype "passive"))
    )
    (net (code "118") (name "unconnected-(U7-GPIO14-Pad13)") (class "Default")
      (node (ref "U7") (pin "13") (pinfunction "GPIO14_13") (pintype "passive"))
    )
    (net (code "119") (name "unconnected-(U7-GPIO15-Pad2)") (class "Default")
      (node (ref "U7") (pin "2") (pinfunction "GPIO15_2") (pintype "passive"))
    )
    (net (code "120") (name "unconnected-(U7-GPIO16-Pad12)") (class "Default")
      (node (ref "U7") (pin "12") (pinfunction "GPIO16_12") (pintype "passive"))
    )
    (net (code "121") (name "unconnected-(U7-MTDO-Pad17)") (class "Default")
      (node (ref "U7") (pin "17") (pinfunction "MTDO_17") (pintype "passive"))
    )
    (net (code "122") (name "unconnected-(U7-MTMS-Pad20)") (class "Default")
      (node (ref "U7") (pin "20") (pinfunction "MTMS_20") (pintype "passive"))
    )
    (net (code "123") (name "unconnected-(U7-RESET-Pad9)") (class "Default")
      (node (ref "U7") (pin "9") (pinfunction "RESET_9") (pintype "passive"))
    )
    (net (code "124") (name "unconnected-(U7-RXD-Pad7)") (class "Default")
      (node (ref "U7") (pin "7") (pinfunction "RXD_7") (pintype "passive"))
    )
    (net (code "125") (name "unconnected-(U101-EN-Pad2)") (class "Default")
      (node (ref "U101") (pin "2") (pinfunction "EN_2") (pintype "passive"))
    )
    (net (code "126") (name "unconnected-(U103-Vout-Pad4)") (class "Default")
      (node (ref "U103") (pin "4") (pinfunction "Vout_4") (pintype "passive"))
    )
    (net (code "127") (name "unconnected-(USB-ID-Pad4)") (class "Default")
      (node (ref "USB") (pin "4") (pinfunction "ID_4") (pintype "passive"))
    )
  )
)
